# testtest.net
KiCad netlist of a schematic drawn in Altium Designer
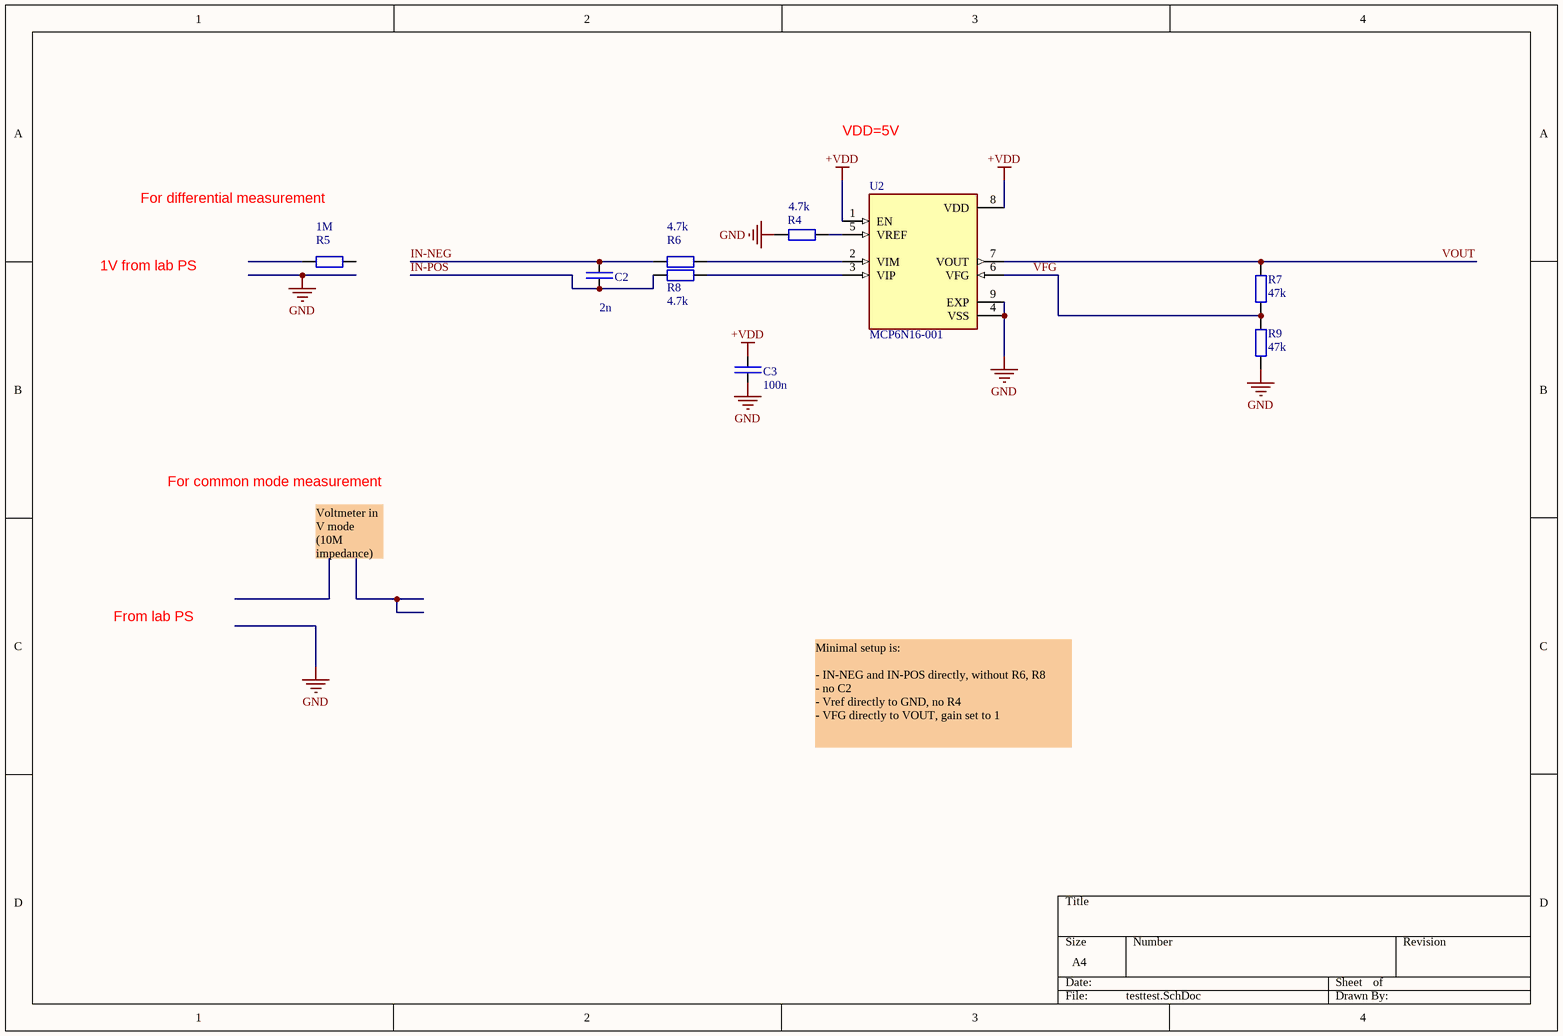
[diagram p0: testtest.SchDoc]

(export (version "E")
  (design (tool "Eeschema 10.0.6"))
  (components
    (comp (ref "C2")
      (value "2n")
      (footprint "Passives:FPR_0402_C_R0")
      (description "Capacitor - generic SMD")
      (fields (field (name "Comment") "PN_C_100n"))
      (libsource (lib "Passives") (part "C"))
    )
    (comp (ref "C3")
      (value "100n")
      (footprint "Passives:FPR_0402_C_R0")
      (description "Capacitor - generic SMD")
      (fields (field (name "Comment") "PN_C_100n"))
      (libsource (lib "Passives") (part "C"))
    )
    (comp (ref "R4")
      (value "4.7k")
      (footprint "Passives:FPR_0402_R_R0")
      (description "Resistor - generic SMD")
      (fields (field (name "Comment") "PN_R_4k7"))
      (libsource (lib "Passives") (part "R"))
    )
    (comp (ref "R5")
      (value "1M")
      (footprint "Passives:FPR_0402_R_R0")
      (description "Resistor - generic SMD")
      (fields (field (name "Comment") "PN_R_4k7"))
      (libsource (lib "Passives") (part "R"))
    )
    (comp (ref "R6")
      (value "4.7k")
      (footprint "Passives:FPR_0402_R_R0")
      (description "Resistor - generic SMD")
      (fields (field (name "Comment") "PN_R_4k7"))
      (libsource (lib "Passives") (part "R"))
    )
    (comp (ref "R7")
      (value "47k")
      (footprint "Passives:FPR_0402_R_R0")
      (description "Resistor - generic SMD")
      (fields (field (name "Comment") "PN_R_4k7"))
      (libsource (lib "Passives") (part "R"))
    )
    (comp (ref "R8")
      (value "4.7k")
      (footprint "Passives:FPR_0402_R_R0")
      (description "Resistor - generic SMD")
      (fields (field (name "Comment") "PN_R_4k7"))
      (libsource (lib "Passives") (part "R"))
    )
    (comp (ref "R9")
      (value "47k")
      (footprint "Passives:FPR_0402_R_R0")
      (description "Resistor - generic SMD")
      (fields (field (name "Comment") "PN_R_4k7"))
      (libsource (lib "Passives") (part "R"))
    )
    (comp (ref "U2")
      (value "MCP6N16-001")
      (footprint "SON65P300X300X100-9N")
      (description "Instrumentation Amplifier 1 Circuit Rail-to-Rail 8-DFN-EP (3x3)")
      (fields (field (name "MP") "MCP6N16-100E/MF") (field (name "MF") "Microchip"))
      (libsource (lib "MCP6N16-100E_MF") (part "MCP6N16-100E/MF"))
    )
  )
  (nets
    (net (code "1") (name "+VDD") (class "Default")
      (node (ref "C3") (pin "2") (pinfunction "2_2") (pintype "passive"))
      (node (ref "U2") (pin "1") (pinfunction "EN_1") (pintype "input"))
      (node (ref "U2") (pin "8") (pinfunction "VDD_8") (pintype "power_in"))
    )
    (net (code "2") (name "/IN-NEG") (class "Default")
      (node (ref "C2") (pin "2") (pinfunction "2_2") (pintype "passive"))
      (node (ref "R6") (pin "2") (pinfunction "2_2") (pintype "passive"))
    )
    (net (code "3") (name "/IN-POS") (class "Default")
      (node (ref "C2") (pin "1") (pinfunction "1_1") (pintype "passive"))
      (node (ref "R8") (pin "2") (pinfunction "2_2") (pintype "passive"))
    )
    (net (code "4") (name "/VFG") (class "Default")
      (node (ref "R7") (pin "2") (pinfunction "2_2") (pintype "passive"))
      (node (ref "R9") (pin "1") (pinfunction "1_1") (pintype "passive"))
      (node (ref "U2") (pin "6") (pinfunction "VFG_6") (pintype "input"))
    )
    (net (code "5") (name "/VOUT") (class "Default")
      (node (ref "R7") (pin "1") (pinfunction "1_1") (pintype "passive"))
      (node (ref "U2") (pin "7") (pinfunction "VOUT_7") (pintype "output"))
    )
    (net (code "6") (name "GND") (class "Default")
      (node (ref "C3") (pin "1") (pinfunction "1_1") (pintype "passive"))
      (node (ref "R4") (pin "2") (pinfunction "2_2") (pintype "passive"))
      (node (ref "R9") (pin "2") (pinfunction "2_2") (pintype "passive"))
      (node (ref "U2") (pin "4") (pinfunction "VSS_4") (pintype "power_in"))
      (node (ref "U2") (pin "9") (pinfunction "EXP_9") (pintype "power_in"))
    )
    (net (code "7") (name "Net-(U2-VIM)") (class "Default")
      (node (ref "R6") (pin "1") (pinfunction "1_1") (pintype "passive"))
      (node (ref "U2") (pin "2") (pinfunction "VIM_2") (pintype "input"))
    )
    (net (code "8") (name "Net-(U2-VIP)") (class "Default")
      (node (ref "R8") (pin "1") (pinfunction "1_1") (pintype "passive"))
      (node (ref "U2") (pin "3") (pinfunction "VIP_3") (pintype "input"))
    )
    (net (code "9") (name "Net-(U2-VREF)") (class "Default")
      (node (ref "R4") (pin "1") (pinfunction "1_1") (pintype "passive"))
      (node (ref "U2") (pin "5") (pinfunction "VREF_5") (pintype "input"))
    )
    (net (code "10") (name "unconnected-(R5-Pad1)") (class "Default")
      (node (ref "R5") (pin "1") (pinfunction "1_1") (pintype "passive"))
    )
    (net (code "11") (name "unconnected-(R5-Pad2)") (class "Default")
      (node (ref "R5") (pin "2") (pinfunction "2_2") (pintype "passive"))
    )
  )
)
